# CC1101_reva.net
KiCad netlist of a schematic drawn in EAGLE
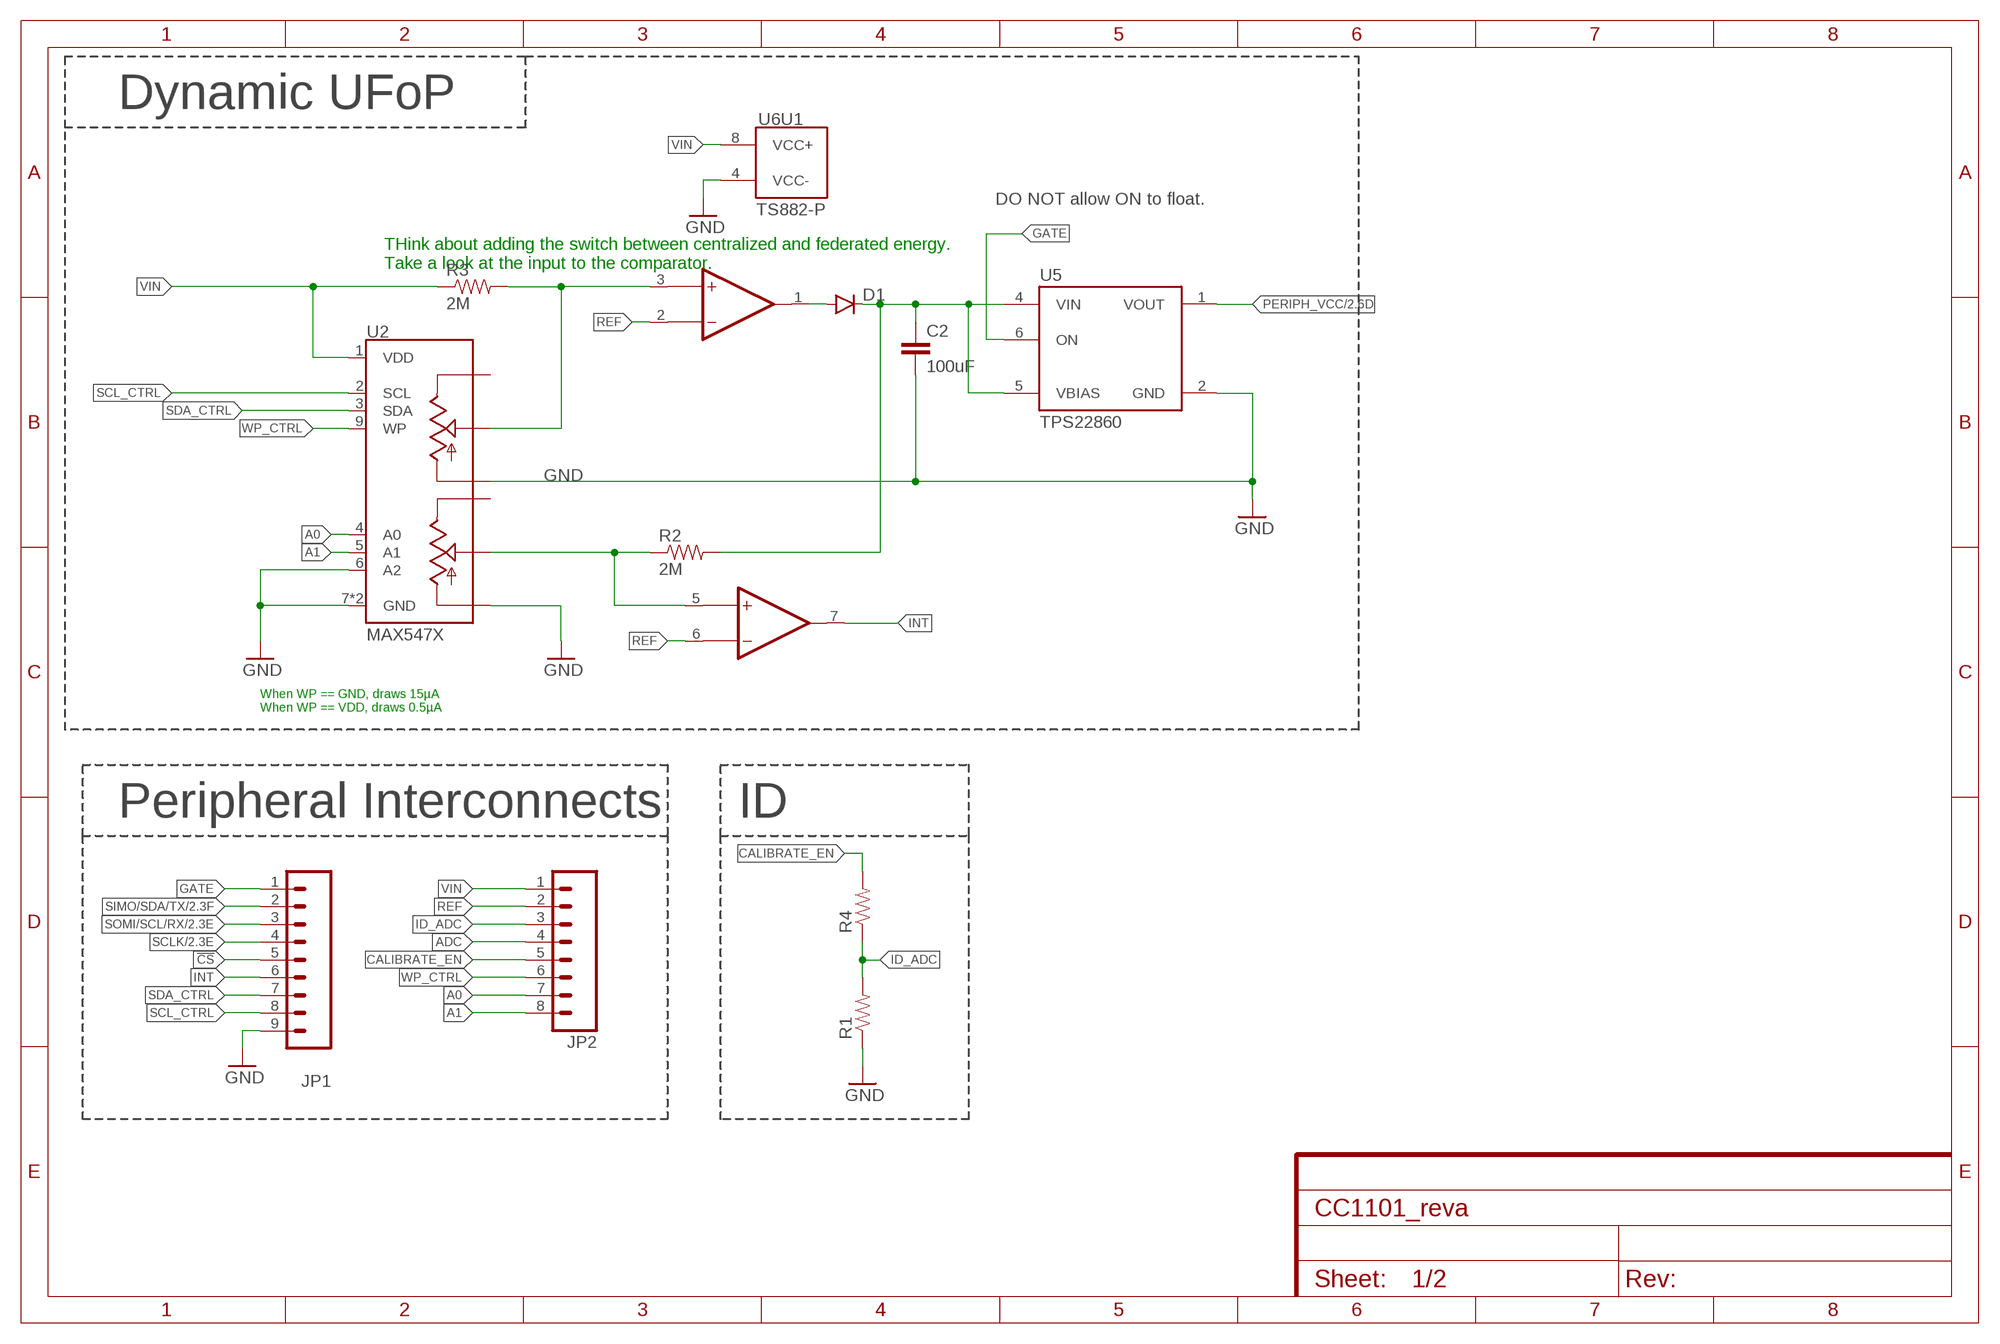
[diagram p0: schematic, sheet 1]
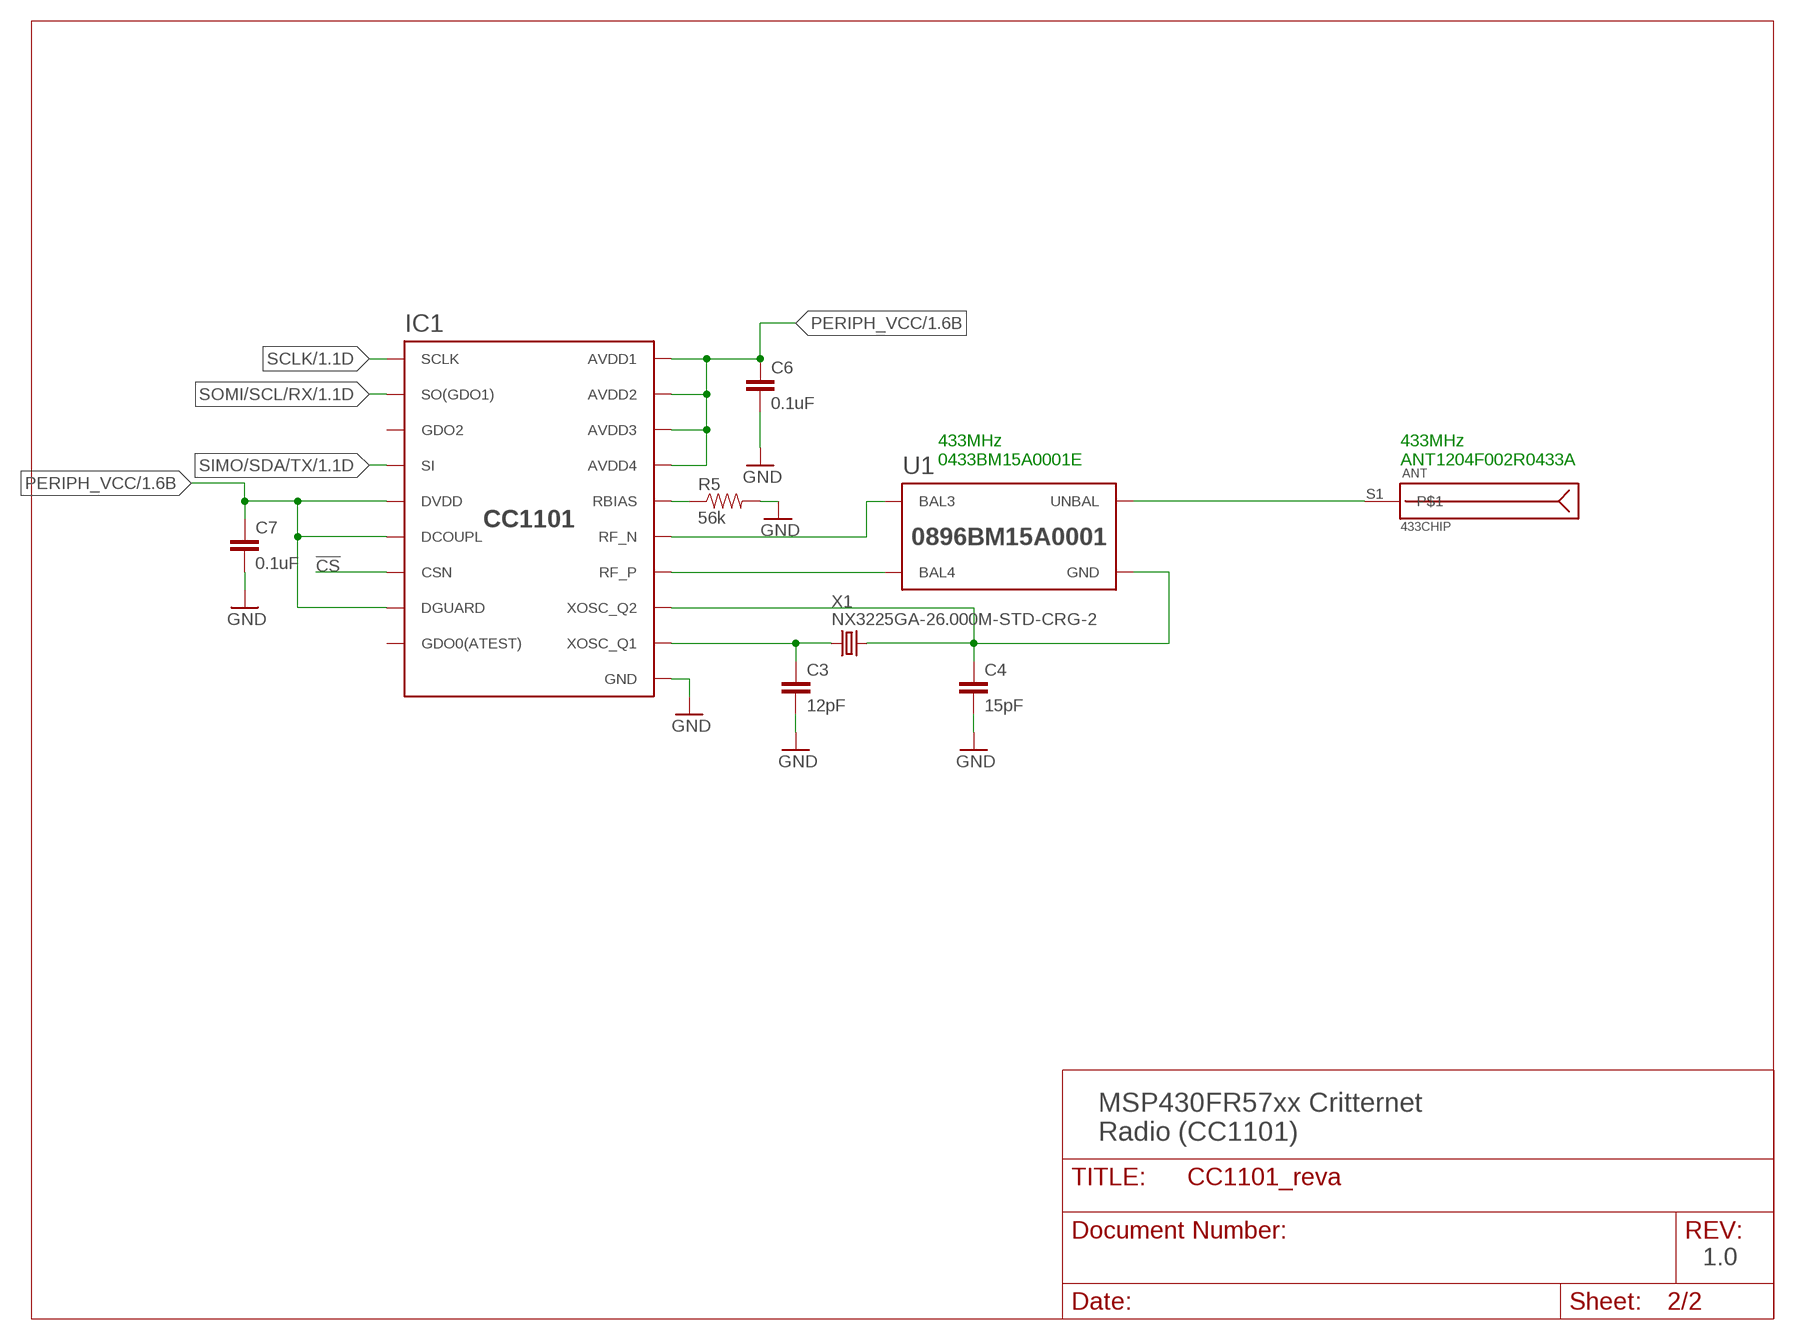
[diagram p1: schematic, sheet 2]

(export (version "E")
  (design (tool "Eeschema 10.0.6"))
  (components
    (comp (ref "ANT")
      (value "433CHIP")
      (footprint "eagle-import:ANT-433-USP")
      (libsource (lib "eagle-import") (part "433CHIP"))
    )
    (comp (ref "C3")
      (value "12pF")
      (footprint "eagle-import:0603")
      (libsource (lib "eagle-import") (part "C-EU0603"))
    )
    (comp (ref "C4")
      (value "15pF")
      (footprint "eagle-import:0603")
      (libsource (lib "eagle-import") (part "C-EU0603"))
    )
    (comp (ref "C6")
      (value "0.1uF")
      (footprint "eagle-import:0603")
      (libsource (lib "eagle-import") (part "C-EU0603"))
    )
    (comp (ref "C7")
      (value "0.1uF")
      (footprint "eagle-import:0603")
      (libsource (lib "eagle-import") (part "C-EU0603"))
    )
    (comp (ref "IC1")
      (value "CC1101")
      (footprint "eagle-import:QLP20")
      (libsource (lib "eagle-import") (part "CC1101"))
    )
    (comp (ref "R5")
      (value "56k")
      (footprint "eagle-import:0603")
      (libsource (lib "eagle-import") (part "R-EU0603"))
    )
    (comp (ref "U1")
      (value "0896BM15A0001")
      (footprint "eagle-import:0896BM15A0001")
      (libsource (lib "eagle-import") (part "0896BM15A0001"))
    )
    (comp (ref "X1")
      (value "NX3225GA-26.000M-STD-CRG-2")
      (footprint "eagle-import:XTAL-3.2X2.5")
      (libsource (lib "eagle-import") (part "XTAL-3.2X2.5"))
    )
    (comp (ref "C2")
      (value "100uF")
      (footprint "eagle-import:1210")
      (libsource (lib "eagle-import") (part "CAP1210"))
    )
    (comp (ref "D1")
      (value "DIODESOD523")
      (footprint "eagle-import:SOD523")
      (libsource (lib "eagle-import") (part "DIODESOD523"))
    )
    (comp (ref "JP1")
      (value "M091.27MM")
      (footprint "eagle-import:1X09-1.27MM")
      (libsource (lib "eagle-import") (part "M091.27MM"))
    )
    (comp (ref "JP2")
      (value "M081.27MM")
      (footprint "eagle-import:1X08-1.27MM")
      (libsource (lib "eagle-import") (part "M081.27MM"))
    )
    (comp (ref "R1")
      (value "R-EU0603")
      (footprint "eagle-import:0603")
      (libsource (lib "eagle-import") (part "R-EU0603"))
    )
    (comp (ref "R2")
      (value "2M")
      (footprint "eagle-import:0603")
      (libsource (lib "eagle-import") (part "R-EU0603"))
    )
    (comp (ref "R3")
      (value "2M")
      (footprint "eagle-import:0603")
      (libsource (lib "eagle-import") (part "R-EU0603"))
    )
    (comp (ref "R4")
      (value "R-EU0603")
      (footprint "eagle-import:0603")
      (libsource (lib "eagle-import") (part "R-EU0603"))
    )
    (comp (ref "U2")
      (value "MAX547X")
      (footprint "eagle-import:QFN16")
      (libsource (lib "eagle-import") (part "MAX547X"))
    )
    (comp (ref "U5")
      (value "TPS22860")
      (footprint "eagle-import:TSOT23-6")
      (libsource (lib "eagle-import") (part "TPS22860"))
    )
    (comp (ref "U6")
      (value "TS882-P")
      (footprint "eagle-import:UDFN8")
      (fields (field (name "DIGIKEY") "497-14073-1-ND"))
      (libsource (lib "eagle-import") (part "TS882-P"))
    )
  )
  (nets
    (net (code "1") (name "A0") (class "Default")
      (node (ref "JP2") (pin "7") (pinfunction "7_7") (pintype "passive"))
      (node (ref "U2") (pin "4") (pinfunction "A0_4") (pintype "bidirectional"))
    )
    (net (code "2") (name "A1") (class "Default")
      (node (ref "JP2") (pin "8") (pinfunction "8_8") (pintype "passive"))
      (node (ref "U2") (pin "5") (pinfunction "A1_5") (pintype "bidirectional"))
    )
    (net (code "3") (name "ADC") (class "Default")
      (node (ref "JP2") (pin "4") (pinfunction "4_4") (pintype "passive"))
    )
    (net (code "4") (name "CALIBRATE_EN") (class "Default")
      (node (ref "JP2") (pin "5") (pinfunction "5_5") (pintype "passive"))
      (node (ref "R4") (pin "2") (pinfunction "2_2") (pintype "passive"))
    )
    (net (code "5") (name "GATE") (class "Default")
      (node (ref "JP1") (pin "1") (pinfunction "1_1") (pintype "passive"))
      (node (ref "U5") (pin "6") (pinfunction "ON_6") (pintype "bidirectional"))
    )
    (net (code "6") (name "GND") (class "Default")
      (node (ref "C2") (pin "2") (pinfunction "2_2") (pintype "passive"))
      (node (ref "C3") (pin "2") (pinfunction "2_2") (pintype "passive"))
      (node (ref "C4") (pin "2") (pinfunction "2_2") (pintype "passive"))
      (node (ref "C6") (pin "2") (pinfunction "2_2") (pintype "passive"))
      (node (ref "C7") (pin "2") (pinfunction "2_2") (pintype "passive"))
      (node (ref "IC1") (pin "16") (pinfunction "GND_16") (pintype "bidirectional"))
      (node (ref "IC1") (pin "19") (pinfunction "GND_19") (pintype "bidirectional"))
      (node (ref "IC1") (pin "GND") (pinfunction "GND_GND") (pintype "bidirectional"))
      (node (ref "JP1") (pin "9") (pinfunction "9_9") (pintype "passive"))
      (node (ref "R1") (pin "1") (pinfunction "1_1") (pintype "passive"))
      (node (ref "R5") (pin "2") (pinfunction "2_2") (pintype "passive"))
      (node (ref "U2") (pin "10") (pinfunction "LB_10") (pintype "bidirectional"))
      (node (ref "U2") (pin "13") (pinfunction "LA_13") (pintype "passive"))
      (node (ref "U2") (pin "6") (pinfunction "A2_6") (pintype "bidirectional"))
      (node (ref "U2") (pin "7") (pinfunction "GND_7") (pintype "bidirectional"))
      (node (ref "U2") (pin "TH") (pinfunction "GND_TH") (pintype "bidirectional"))
      (node (ref "U5") (pin "2") (pinfunction "GND_2") (pintype "bidirectional"))
      (node (ref "U6") (pin "4") (pinfunction "VCC-_4") (pintype "bidirectional"))
    )
    (net (code "7") (name "ID_ADC") (class "Default")
      (node (ref "JP2") (pin "3") (pinfunction "3_3") (pintype "passive"))
      (node (ref "R1") (pin "2") (pinfunction "2_2") (pintype "passive"))
      (node (ref "R4") (pin "1") (pinfunction "1_1") (pintype "passive"))
    )
    (net (code "8") (name "INT") (class "Default")
      (node (ref "JP1") (pin "6") (pinfunction "6_6") (pintype "passive"))
      (node (ref "U6") (pin "7") (pinfunction "OUT1_7") (pintype "output"))
    )
    (net (code "9") (name "Net-(ANT-P$1)") (class "Default")
      (node (ref "ANT") (pin "S1") (pinfunction "P$1_S1") (pintype "bidirectional"))
      (node (ref "U1") (pin "1") (pinfunction "UNBAL_1") (pintype "bidirectional"))
    )
    (net (code "10") (name "Net-(IC1-RBIAS)") (class "Default")
      (node (ref "IC1") (pin "17") (pinfunction "RBIAS_17") (pintype "bidirectional"))
      (node (ref "R5") (pin "1") (pinfunction "1_1") (pintype "passive"))
    )
    (net (code "11") (name "Net-(IC1-RF_N)") (class "Default")
      (node (ref "IC1") (pin "13") (pinfunction "RF_N_13") (pintype "bidirectional"))
      (node (ref "U1") (pin "3") (pinfunction "BAL3_3") (pintype "bidirectional"))
    )
    (net (code "12") (name "Net-(IC1-RF_P)") (class "Default")
      (node (ref "IC1") (pin "12") (pinfunction "RF_P_12") (pintype "bidirectional"))
      (node (ref "U1") (pin "4") (pinfunction "BAL4_4") (pintype "bidirectional"))
    )
    (net (code "13") (name "Net-(IC1-XOSC_Q1)") (class "Default")
      (node (ref "C3") (pin "1") (pinfunction "1_1") (pintype "passive"))
      (node (ref "IC1") (pin "8") (pinfunction "XOSC_Q1_8") (pintype "bidirectional"))
      (node (ref "X1") (pin "1") (pinfunction "1_1") (pintype "passive"))
    )
    (net (code "14") (name "Net-(IC1-XOSC_Q2)") (class "Default")
      (node (ref "C4") (pin "1") (pinfunction "1_1") (pintype "passive"))
      (node (ref "IC1") (pin "10") (pinfunction "XOSC_Q2_10") (pintype "bidirectional"))
      (node (ref "U1") (pin "2") (pinfunction "GND_2") (pintype "bidirectional"))
      (node (ref "U1") (pin "5") (pinfunction "GND_5") (pintype "bidirectional"))
      (node (ref "U1") (pin "6") (pinfunction "GND_6") (pintype "bidirectional"))
      (node (ref "X1") (pin "3") (pinfunction "2_3") (pintype "passive"))
    )
    (net (code "15") (name "Net-(U2-WA)") (class "Default")
      (node (ref "R3") (pin "2") (pinfunction "2_2") (pintype "passive"))
      (node (ref "U2") (pin "14") (pinfunction "WA_14") (pintype "passive"))
      (node (ref "U6") (pin "3") (pinfunction "IN1+_3") (pintype "input"))
    )
    (net (code "16") (name "Net-(U2-WB)") (class "Default")
      (node (ref "R2") (pin "1") (pinfunction "1_1") (pintype "passive"))
      (node (ref "U2") (pin "11") (pinfunction "WB_11") (pintype "bidirectional"))
      (node (ref "U6") (pin "5") (pinfunction "IN1+_5") (pintype "input"))
    )
    (net (code "17") (name "Net-(U5-VBIAS)") (class "Default")
      (node (ref "C2") (pin "1") (pinfunction "1_1") (pintype "passive"))
      (node (ref "D1") (pin "C") (pinfunction "C_C") (pintype "passive"))
      (node (ref "R2") (pin "2") (pinfunction "2_2") (pintype "passive"))
      (node (ref "U5") (pin "4") (pinfunction "VIN_4") (pintype "bidirectional"))
      (node (ref "U5") (pin "5") (pinfunction "VBIAS_5") (pintype "bidirectional"))
    )
    (net (code "18") (name "Net-(U6A-OUT1)") (class "Default")
      (node (ref "D1") (pin "A") (pinfunction "A_A") (pintype "passive"))
      (node (ref "U6") (pin "1") (pinfunction "OUT1_1") (pintype "output"))
    )
    (net (code "19") (name "PERIPH_VCC") (class "Default")
      (node (ref "C6") (pin "1") (pinfunction "1_1") (pintype "passive"))
      (node (ref "C7") (pin "1") (pinfunction "1_1") (pintype "passive"))
      (node (ref "IC1") (pin "11") (pinfunction "AVDD2_11") (pintype "bidirectional"))
      (node (ref "IC1") (pin "14") (pinfunction "AVDD3_14") (pintype "bidirectional"))
      (node (ref "IC1") (pin "15") (pinfunction "AVDD4_15") (pintype "bidirectional"))
      (node (ref "IC1") (pin "18") (pinfunction "DGUARD_18") (pintype "bidirectional"))
      (node (ref "IC1") (pin "4") (pinfunction "DVDD_4") (pintype "bidirectional"))
      (node (ref "IC1") (pin "5") (pinfunction "DCOUPL_5") (pintype "bidirectional"))
      (node (ref "IC1") (pin "9") (pinfunction "AVDD1_9") (pintype "bidirectional"))
      (node (ref "U5") (pin "1") (pinfunction "VOUT_1") (pintype "bidirectional"))
    )
    (net (code "20") (name "REF") (class "Default")
      (node (ref "JP2") (pin "2") (pinfunction "2_2") (pintype "passive"))
      (node (ref "U6") (pin "2") (pinfunction "IN1-_2") (pintype "input"))
      (node (ref "U6") (pin "6") (pinfunction "IN1-_6") (pintype "input"))
    )
    (net (code "21") (name "SCLK") (class "Default")
      (node (ref "IC1") (pin "1") (pinfunction "SCLK_1") (pintype "bidirectional"))
      (node (ref "JP1") (pin "4") (pinfunction "4_4") (pintype "passive"))
    )
    (net (code "22") (name "SCL_CTRL") (class "Default")
      (node (ref "JP1") (pin "8") (pinfunction "8_8") (pintype "passive"))
      (node (ref "U2") (pin "2") (pinfunction "SCL_2") (pintype "bidirectional"))
    )
    (net (code "23") (name "SDA_CTRL") (class "Default")
      (node (ref "JP1") (pin "7") (pinfunction "7_7") (pintype "passive"))
      (node (ref "U2") (pin "3") (pinfunction "SDA_3") (pintype "bidirectional"))
    )
    (net (code "24") (name "SIMO{slash}SDA{slash}TX") (class "Default")
      (node (ref "IC1") (pin "20") (pinfunction "SI_20") (pintype "bidirectional"))
      (node (ref "JP1") (pin "2") (pinfunction "2_2") (pintype "passive"))
    )
    (net (code "25") (name "SOMI{slash}SCL{slash}RX") (class "Default")
      (node (ref "IC1") (pin "2") (pinfunction "SO(GDO1)_2") (pintype "bidirectional"))
      (node (ref "JP1") (pin "3") (pinfunction "3_3") (pintype "passive"))
    )
    (net (code "26") (name "VIN") (class "Default")
      (node (ref "JP2") (pin "1") (pinfunction "1_1") (pintype "passive"))
      (node (ref "R3") (pin "1") (pinfunction "1_1") (pintype "passive"))
      (node (ref "U2") (pin "1") (pinfunction "VDD_1") (pintype "bidirectional"))
      (node (ref "U6") (pin "8") (pinfunction "VCC+_8") (pintype "bidirectional"))
    )
    (net (code "27") (name "WP_CTRL") (class "Default")
      (node (ref "JP2") (pin "6") (pinfunction "6_6") (pintype "passive"))
      (node (ref "U2") (pin "9") (pinfunction "WP_9") (pintype "bidirectional"))
    )
    (net (code "28") (name "unconnected-(IC1-GDO0(ATEST)-Pad6)") (class "Default")
      (node (ref "IC1") (pin "6") (pinfunction "GDO0(ATEST)_6") (pintype "bidirectional"))
    )
    (net (code "29") (name "unconnected-(IC1-GDO2-Pad3)") (class "Default")
      (node (ref "IC1") (pin "3") (pinfunction "GDO2_3") (pintype "bidirectional"))
    )
    (net (code "30") (name "unconnected-(U2-HA-Pad15)") (class "Default")
      (node (ref "U2") (pin "15") (pinfunction "HA_15") (pintype "passive"))
    )
    (net (code "31") (name "unconnected-(U2-HB-Pad12)") (class "Default")
      (node (ref "U2") (pin "12") (pinfunction "HB_12") (pintype "bidirectional"))
    )
    (net (code "32") (name "~{CS}") (class "Default")
      (node (ref "IC1") (pin "7") (pinfunction "CSN_7") (pintype "bidirectional"))
      (node (ref "JP1") (pin "5") (pinfunction "5_5") (pintype "passive"))
    )
  )
)
